# OPA_BOARD_V2.net
KiCad netlist of a schematic drawn in EAGLE
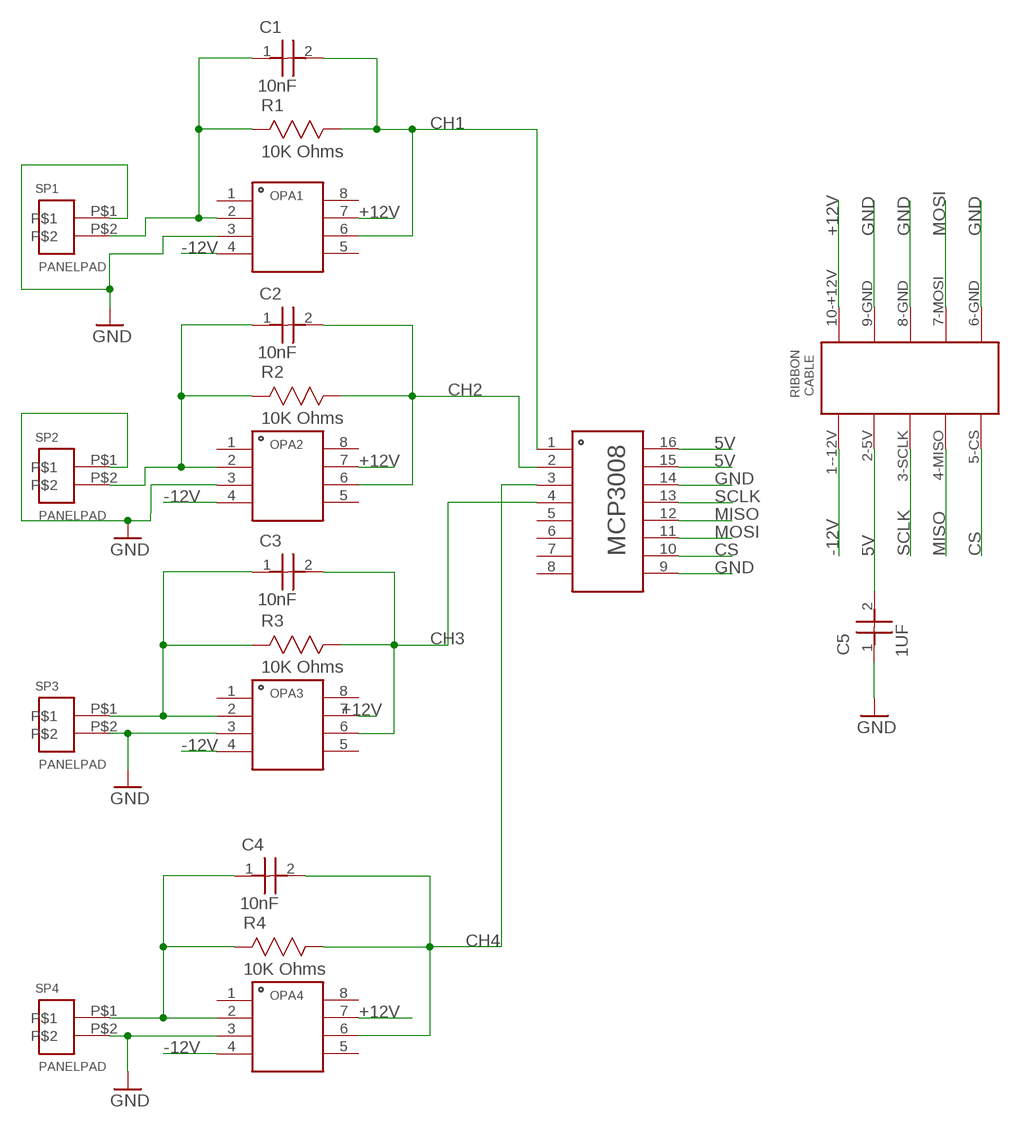
[diagram p0: schematic, sheet 1]

(export (version "E")
  (design (tool "Eeschema 10.0.6"))
  (components
    (comp (ref "ADC")
      (value "MCP3008-SOIC16")
      (footprint "eagle-import:SOIC16N")
      (libsource (lib "eagle-import") (part "MCP3008-SOIC16"))
    )
    (comp (ref "C1")
      (value "10nF")
      (footprint "eagle-import:CAP1206")
      (fields (field (name "MPN") "C1206C103K5RACTU") (field (name "TOLERANCE") "±10%"))
      (libsource (lib "eagle-import") (part "CAP1206"))
    )
    (comp (ref "C2")
      (value "10nF")
      (footprint "eagle-import:CAP1206")
      (fields (field (name "MPN") "C1206C103K5RACTU") (field (name "TOLERANCE") "±10%"))
      (libsource (lib "eagle-import") (part "CAP1206"))
    )
    (comp (ref "C3")
      (value "10nF")
      (footprint "eagle-import:CAP1206")
      (fields (field (name "MPN") "C1206C103K5RACTU") (field (name "TOLERANCE") "±10%"))
      (libsource (lib "eagle-import") (part "CAP1206"))
    )
    (comp (ref "C4")
      (value "10nF")
      (footprint "eagle-import:CAP1206")
      (fields (field (name "MPN") "C1206C103K5RACTU") (field (name "TOLERANCE") "±10%"))
      (libsource (lib "eagle-import") (part "CAP1206"))
    )
    (comp (ref "C5")
      (value "1UF")
      (footprint "eagle-import:CAP1206")
      (fields (field (name "MPN") "C1206C103K5RACTU") (field (name "TOLERANCE") "±10%"))
      (libsource (lib "eagle-import") (part "CAP1206"))
    )
    (comp (ref "OPA1")
      (value "THS4631-SOIC8")
      (footprint "eagle-import:SOIC8")
      (libsource (lib "eagle-import") (part "THS4631-SOIC8"))
    )
    (comp (ref "OPA2")
      (value "THS4631-SOIC8")
      (footprint "eagle-import:SOIC8")
      (libsource (lib "eagle-import") (part "THS4631-SOIC8"))
    )
    (comp (ref "OPA3")
      (value "THS4631-SOIC8")
      (footprint "eagle-import:SOIC8")
      (libsource (lib "eagle-import") (part "THS4631-SOIC8"))
    )
    (comp (ref "OPA4")
      (value "THS4631-SOIC8")
      (footprint "eagle-import:SOIC8")
      (libsource (lib "eagle-import") (part "THS4631-SOIC8"))
    )
    (comp (ref "R1")
      (value "10K Ohms")
      (footprint "eagle-import:RES1206")
      (fields (field (name "MPN") "CRCW120610K0FKEA") (field (name "TOLERANCE") "±1%"))
      (libsource (lib "eagle-import") (part "RES1206"))
    )
    (comp (ref "R2")
      (value "10K Ohms")
      (footprint "eagle-import:RES1206")
      (fields (field (name "MPN") "CRCW120610K0FKEA") (field (name "TOLERANCE") "±1%"))
      (libsource (lib "eagle-import") (part "RES1206"))
    )
    (comp (ref "R3")
      (value "10K Ohms")
      (footprint "eagle-import:RES1206")
      (fields (field (name "MPN") "CRCW120610K0FKEA") (field (name "TOLERANCE") "±1%"))
      (libsource (lib "eagle-import") (part "RES1206"))
    )
    (comp (ref "R4")
      (value "10K Ohms")
      (footprint "eagle-import:RES1206")
      (fields (field (name "MPN") "CRCW120610K0FKEA") (field (name "TOLERANCE") "±1%"))
      (libsource (lib "eagle-import") (part "RES1206"))
    )
    (comp (ref "SP1")
      (value "PANELPAD")
      (footprint "eagle-import:PANELPADS")
      (libsource (lib "eagle-import") (part "PANELPAD"))
    )
    (comp (ref "SP2")
      (value "PANELPAD")
      (footprint "eagle-import:PANELPADS")
      (libsource (lib "eagle-import") (part "PANELPAD"))
    )
    (comp (ref "SP3")
      (value "PANELPAD")
      (footprint "eagle-import:PANELPADS")
      (libsource (lib "eagle-import") (part "PANELPAD"))
    )
    (comp (ref "SP4")
      (value "PANELPAD")
      (footprint "eagle-import:PANELPADS")
      (libsource (lib "eagle-import") (part "PANELPAD"))
    )
    (comp (ref "U$1")
      (value "5X2RIBBONCONNECTOR")
      (footprint "eagle-import:5X2RIBBONCONNECTOR")
      (libsource (lib "eagle-import") (part "5X2RIBBONCONNECTOR"))
    )
  )
  (nets
    (net (code "1") (name "/+12V") (class "Default")
      (node (ref "OPA1") (pin "7") (pinfunction "7-VS+_7") (pintype "bidirectional"))
      (node (ref "OPA2") (pin "7") (pinfunction "7-VS+_7") (pintype "bidirectional"))
      (node (ref "OPA3") (pin "7") (pinfunction "7-VS+_7") (pintype "bidirectional"))
      (node (ref "OPA4") (pin "7") (pinfunction "7-VS+_7") (pintype "bidirectional"))
      (node (ref "U$1") (pin "10-+12V") (pinfunction "10-+12V_10-+12V") (pintype "bidirectional"))
    )
    (net (code "2") (name "/-12V") (class "Default")
      (node (ref "OPA1") (pin "4") (pinfunction "4-VS-_4") (pintype "bidirectional"))
      (node (ref "OPA2") (pin "4") (pinfunction "4-VS-_4") (pintype "bidirectional"))
      (node (ref "OPA3") (pin "4") (pinfunction "4-VS-_4") (pintype "bidirectional"))
      (node (ref "OPA4") (pin "4") (pinfunction "4-VS-_4") (pintype "bidirectional"))
      (node (ref "U$1") (pin "1--12V") (pinfunction "1--12V_1--12V") (pintype "bidirectional"))
    )
    (net (code "3") (name "/5V") (class "Default")
      (node (ref "ADC") (pin "15") (pinfunction "15-VREF_15") (pintype "bidirectional"))
      (node (ref "ADC") (pin "16") (pinfunction "16-VDD_16") (pintype "bidirectional"))
      (node (ref "C5") (pin "2") (pinfunction "P$2_2") (pintype "bidirectional"))
      (node (ref "U$1") (pin "2-5V") (pinfunction "2-5V_2-5V") (pintype "bidirectional"))
    )
    (net (code "4") (name "/CH1") (class "Default")
      (node (ref "ADC") (pin "1") (pinfunction "1-CH0_1") (pintype "bidirectional"))
      (node (ref "C1") (pin "2") (pinfunction "P$2_2") (pintype "bidirectional"))
      (node (ref "OPA1") (pin "6") (pinfunction "6-VOUT_6") (pintype "bidirectional"))
      (node (ref "R1") (pin "1") (pinfunction "1_1") (pintype "passive"))
    )
    (net (code "5") (name "/CH2") (class "Default")
      (node (ref "ADC") (pin "2") (pinfunction "2-CH1_2") (pintype "bidirectional"))
      (node (ref "C2") (pin "2") (pinfunction "P$2_2") (pintype "bidirectional"))
      (node (ref "OPA2") (pin "6") (pinfunction "6-VOUT_6") (pintype "bidirectional"))
      (node (ref "R2") (pin "1") (pinfunction "1_1") (pintype "passive"))
    )
    (net (code "6") (name "/CH3") (class "Default")
      (node (ref "ADC") (pin "4") (pinfunction "4-CH3_4") (pintype "bidirectional"))
      (node (ref "C3") (pin "2") (pinfunction "P$2_2") (pintype "bidirectional"))
      (node (ref "OPA3") (pin "6") (pinfunction "6-VOUT_6") (pintype "bidirectional"))
      (node (ref "R3") (pin "1") (pinfunction "1_1") (pintype "passive"))
    )
    (net (code "7") (name "/CH4") (class "Default")
      (node (ref "ADC") (pin "3") (pinfunction "3-CH2_3") (pintype "bidirectional"))
      (node (ref "C4") (pin "2") (pinfunction "P$2_2") (pintype "bidirectional"))
      (node (ref "OPA4") (pin "6") (pinfunction "6-VOUT_6") (pintype "bidirectional"))
      (node (ref "R4") (pin "1") (pinfunction "1_1") (pintype "passive"))
    )
    (net (code "8") (name "/CS") (class "Default")
      (node (ref "ADC") (pin "10") (pinfunction "10-CS_10") (pintype "bidirectional"))
      (node (ref "U$1") (pin "5-CS") (pinfunction "5-CS_5-CS") (pintype "bidirectional"))
    )
    (net (code "9") (name "/MISO") (class "Default")
      (node (ref "ADC") (pin "12") (pinfunction "12-DOUT_12") (pintype "bidirectional"))
      (node (ref "U$1") (pin "4-MISO") (pinfunction "4-MISO_4-MISO") (pintype "bidirectional"))
    )
    (net (code "10") (name "/MOSI") (class "Default")
      (node (ref "ADC") (pin "11") (pinfunction "11-DIN_11") (pintype "bidirectional"))
      (node (ref "U$1") (pin "7-MOSI") (pinfunction "7-MOSI_7-MOSI") (pintype "bidirectional"))
    )
    (net (code "11") (name "/SCLK") (class "Default")
      (node (ref "ADC") (pin "13") (pinfunction "13-CLK_13") (pintype "bidirectional"))
      (node (ref "U$1") (pin "3-SCLK") (pinfunction "3-SCLK_3-SCLK") (pintype "bidirectional"))
    )
    (net (code "12") (name "GND") (class "Default")
      (node (ref "ADC") (pin "14") (pinfunction "14-AGND_14") (pintype "bidirectional"))
      (node (ref "ADC") (pin "9") (pinfunction "9-DGND_9") (pintype "bidirectional"))
      (node (ref "C5") (pin "1") (pinfunction "P$1_1") (pintype "bidirectional"))
      (node (ref "OPA1") (pin "3") (pinfunction "3-VIN+_3") (pintype "bidirectional"))
      (node (ref "OPA2") (pin "3") (pinfunction "3-VIN+_3") (pintype "bidirectional"))
      (node (ref "OPA3") (pin "3") (pinfunction "3-VIN+_3") (pintype "bidirectional"))
      (node (ref "OPA4") (pin "3") (pinfunction "3-VIN+_3") (pintype "bidirectional"))
      (node (ref "SP1") (pin "P$1") (pinfunction "P$1_P$1") (pintype "bidirectional"))
      (node (ref "SP2") (pin "P$1") (pinfunction "P$1_P$1") (pintype "bidirectional"))
      (node (ref "SP3") (pin "P$2") (pinfunction "P$2_P$2") (pintype "bidirectional"))
      (node (ref "SP4") (pin "P$2") (pinfunction "P$2_P$2") (pintype "bidirectional"))
      (node (ref "U$1") (pin "6-GND") (pinfunction "6-GND_6-GND") (pintype "bidirectional"))
      (node (ref "U$1") (pin "8-GND") (pinfunction "8-GND_8-GND") (pintype "bidirectional"))
      (node (ref "U$1") (pin "9-GND") (pinfunction "9-GND_9-GND") (pintype "bidirectional"))
    )
    (net (code "13") (name "Net-(C1-P$1)") (class "Default")
      (node (ref "C1") (pin "1") (pinfunction "P$1_1") (pintype "bidirectional"))
      (node (ref "OPA1") (pin "2") (pinfunction "2-VIN-_2") (pintype "bidirectional"))
      (node (ref "R1") (pin "2") (pinfunction "2_2") (pintype "passive"))
      (node (ref "SP1") (pin "P$2") (pinfunction "P$2_P$2") (pintype "bidirectional"))
    )
    (net (code "14") (name "Net-(C2-P$1)") (class "Default")
      (node (ref "C2") (pin "1") (pinfunction "P$1_1") (pintype "bidirectional"))
      (node (ref "OPA2") (pin "2") (pinfunction "2-VIN-_2") (pintype "bidirectional"))
      (node (ref "R2") (pin "2") (pinfunction "2_2") (pintype "passive"))
      (node (ref "SP2") (pin "P$2") (pinfunction "P$2_P$2") (pintype "bidirectional"))
    )
    (net (code "15") (name "Net-(C3-P$1)") (class "Default")
      (node (ref "C3") (pin "1") (pinfunction "P$1_1") (pintype "bidirectional"))
      (node (ref "OPA3") (pin "2") (pinfunction "2-VIN-_2") (pintype "bidirectional"))
      (node (ref "R3") (pin "2") (pinfunction "2_2") (pintype "passive"))
      (node (ref "SP3") (pin "P$1") (pinfunction "P$1_P$1") (pintype "bidirectional"))
    )
    (net (code "16") (name "Net-(C4-P$1)") (class "Default")
      (node (ref "C4") (pin "1") (pinfunction "P$1_1") (pintype "bidirectional"))
      (node (ref "OPA4") (pin "2") (pinfunction "2-VIN-_2") (pintype "bidirectional"))
      (node (ref "R4") (pin "2") (pinfunction "2_2") (pintype "passive"))
      (node (ref "SP4") (pin "P$1") (pinfunction "P$1_P$1") (pintype "bidirectional"))
    )
    (net (code "17") (name "unconnected-(ADC-5-CH4-Pad5)") (class "Default")
      (node (ref "ADC") (pin "5") (pinfunction "5-CH4_5") (pintype "bidirectional"))
    )
    (net (code "18") (name "unconnected-(ADC-6-CH5-Pad6)") (class "Default")
      (node (ref "ADC") (pin "6") (pinfunction "6-CH5_6") (pintype "bidirectional"))
    )
    (net (code "19") (name "unconnected-(ADC-7-CH6-Pad7)") (class "Default")
      (node (ref "ADC") (pin "7") (pinfunction "7-CH6_7") (pintype "bidirectional"))
    )
    (net (code "20") (name "unconnected-(ADC-8-CH7-Pad8)") (class "Default")
      (node (ref "ADC") (pin "8") (pinfunction "8-CH7_8") (pintype "bidirectional"))
    )
    (net (code "21") (name "unconnected-(OPA1-1-NC-Pad1)") (class "Default")
      (node (ref "OPA1") (pin "1") (pinfunction "1-NC_1") (pintype "bidirectional"))
    )
    (net (code "22") (name "unconnected-(OPA1-5-NC-Pad5)") (class "Default")
      (node (ref "OPA1") (pin "5") (pinfunction "5-NC_5") (pintype "bidirectional"))
    )
    (net (code "23") (name "unconnected-(OPA1-8-NC-Pad8)") (class "Default")
      (node (ref "OPA1") (pin "8") (pinfunction "8-NC_8") (pintype "bidirectional"))
    )
    (net (code "24") (name "unconnected-(OPA2-1-NC-Pad1)") (class "Default")
      (node (ref "OPA2") (pin "1") (pinfunction "1-NC_1") (pintype "bidirectional"))
    )
    (net (code "25") (name "unconnected-(OPA2-5-NC-Pad5)") (class "Default")
      (node (ref "OPA2") (pin "5") (pinfunction "5-NC_5") (pintype "bidirectional"))
    )
    (net (code "26") (name "unconnected-(OPA2-8-NC-Pad8)") (class "Default")
      (node (ref "OPA2") (pin "8") (pinfunction "8-NC_8") (pintype "bidirectional"))
    )
    (net (code "27") (name "unconnected-(OPA3-1-NC-Pad1)") (class "Default")
      (node (ref "OPA3") (pin "1") (pinfunction "1-NC_1") (pintype "bidirectional"))
    )
    (net (code "28") (name "unconnected-(OPA3-5-NC-Pad5)") (class "Default")
      (node (ref "OPA3") (pin "5") (pinfunction "5-NC_5") (pintype "bidirectional"))
    )
    (net (code "29") (name "unconnected-(OPA3-8-NC-Pad8)") (class "Default")
      (node (ref "OPA3") (pin "8") (pinfunction "8-NC_8") (pintype "bidirectional"))
    )
    (net (code "30") (name "unconnected-(OPA4-1-NC-Pad1)") (class "Default")
      (node (ref "OPA4") (pin "1") (pinfunction "1-NC_1") (pintype "bidirectional"))
    )
    (net (code "31") (name "unconnected-(OPA4-5-NC-Pad5)") (class "Default")
      (node (ref "OPA4") (pin "5") (pinfunction "5-NC_5") (pintype "bidirectional"))
    )
    (net (code "32") (name "unconnected-(OPA4-8-NC-Pad8)") (class "Default")
      (node (ref "OPA4") (pin "8") (pinfunction "8-NC_8") (pintype "bidirectional"))
    )
  )
)
